# F280041.net
KiCad netlist of a schematic drawn in Altium Designer
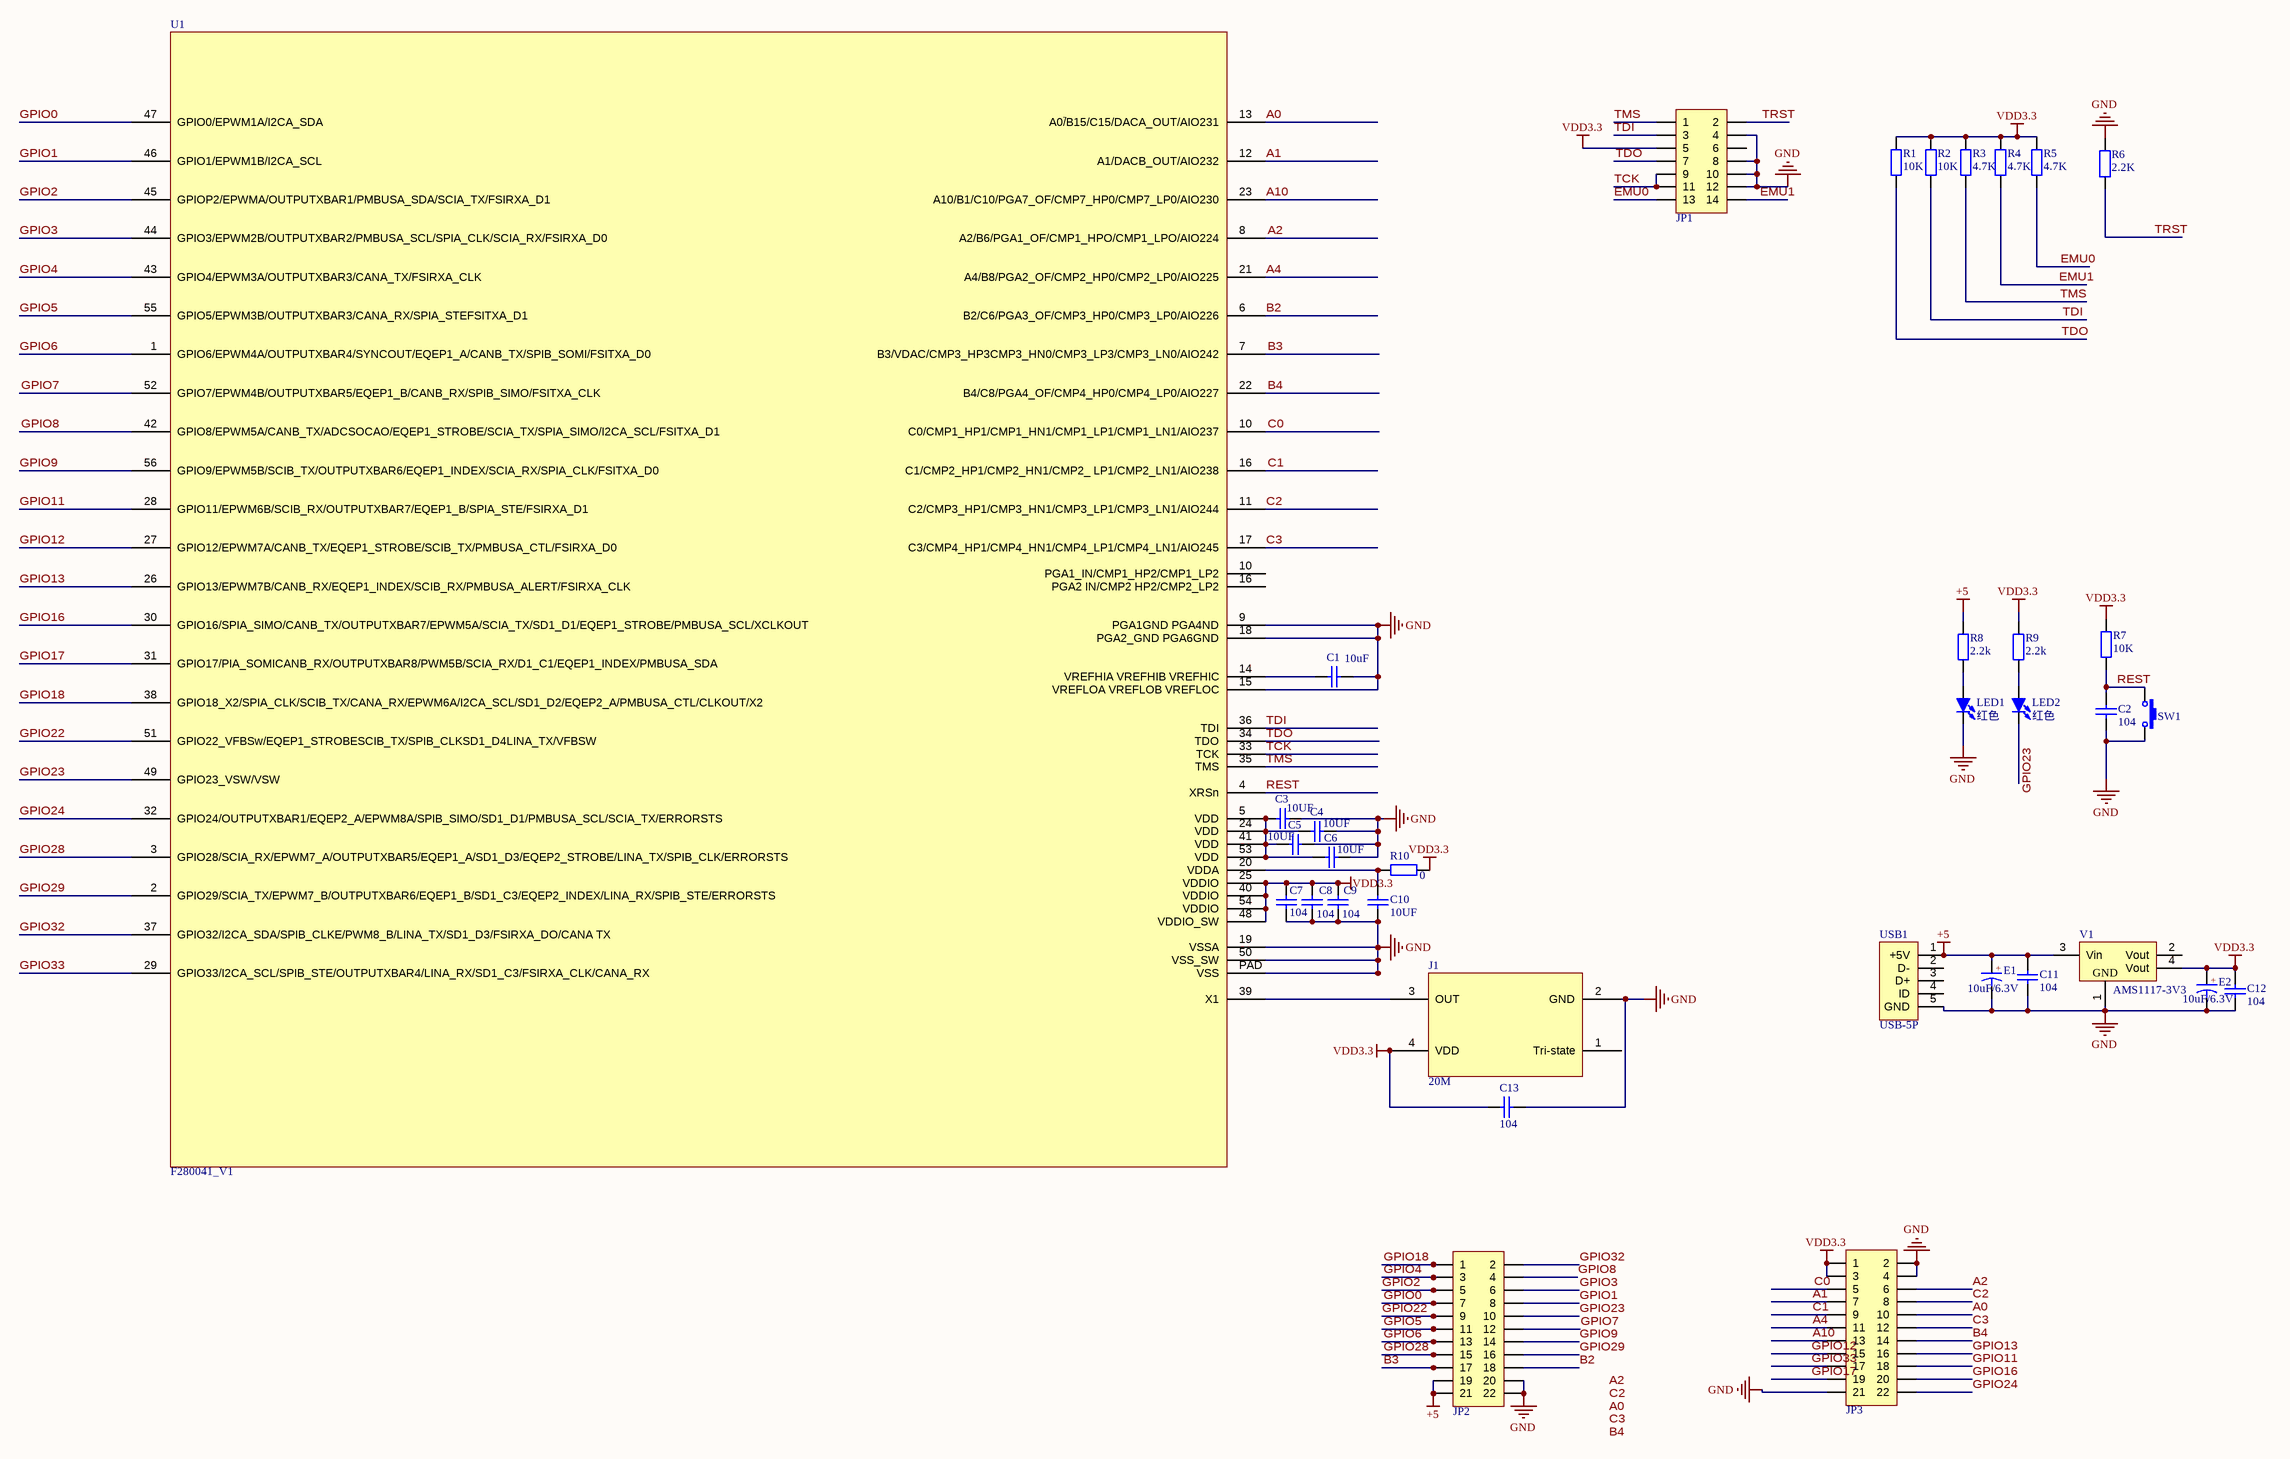
[diagram p0: F280041.SchDoc]

(export (version "E")
  (design (tool "Eeschema 10.0.6"))
  (components
    (comp (ref "C1")
      (value "10uF")
      (footprint "C0603_M")
      (description "贴片电容")
      (libsource (lib "0.1 - 电阻-电容-电感-磁珠-电位器") (part "C"))
    )
    (comp (ref "C2")
      (value "104")
      (footprint "C0603_M")
      (description "贴片电容")
      (libsource (lib "0.1 - 电阻-电容-电感-磁珠-电位器") (part "C"))
    )
    (comp (ref "C3")
      (value "10UF")
      (footprint "C0603_M")
      (description "贴片电容")
      (libsource (lib "0.1 - 电阻-电容-电感-磁珠-电位器") (part "C"))
    )
    (comp (ref "C4")
      (value "10UF")
      (footprint "C0603_M")
      (description "贴片电容")
      (libsource (lib "0.1 - 电阻-电容-电感-磁珠-电位器") (part "C"))
    )
    (comp (ref "C5")
      (value "10UF")
      (footprint "C0603_M")
      (description "贴片电容")
      (libsource (lib "0.1 - 电阻-电容-电感-磁珠-电位器") (part "C"))
    )
    (comp (ref "C6")
      (value "10UF")
      (footprint "C0603_M")
      (description "贴片电容")
      (libsource (lib "0.1 - 电阻-电容-电感-磁珠-电位器") (part "C"))
    )
    (comp (ref "C7")
      (value "104")
      (footprint "C0603_M")
      (description "贴片电容")
      (libsource (lib "0.1 - 电阻-电容-电感-磁珠-电位器") (part "C"))
    )
    (comp (ref "C8")
      (value "104")
      (footprint "C0603_M")
      (description "贴片电容")
      (libsource (lib "0.1 - 电阻-电容-电感-磁珠-电位器") (part "C"))
    )
    (comp (ref "C9")
      (value "104")
      (footprint "C0603_M")
      (description "贴片电容")
      (libsource (lib "0.1 - 电阻-电容-电感-磁珠-电位器") (part "C"))
    )
    (comp (ref "C10")
      (value "10UF")
      (footprint "C0603_M")
      (description "贴片电容")
      (libsource (lib "0.1 - 电阻-电容-电感-磁珠-电位器") (part "C"))
    )
    (comp (ref "C11")
      (value "104")
      (footprint "C0603_M")
      (description "贴片电容")
      (libsource (lib "0.1 - 电阻-电容-电感-磁珠-电位器") (part "C"))
    )
    (comp (ref "C12")
      (value "104")
      (footprint "C0603_M")
      (description "贴片电容")
      (libsource (lib "0.1 - 电阻-电容-电感-磁珠-电位器") (part "C"))
    )
    (comp (ref "C13")
      (value "104")
      (footprint "C0603_M")
      (description "贴片电容")
      (libsource (lib "0.1 - 电阻-电容-电感-磁珠-电位器") (part "C"))
    )
    (comp (ref "E1")
      (value "10uF/6.3V")
      (footprint "C_3216")
      (description "贴片钽电容")
      (libsource (lib "0.1 - 电阻-电容-电感-磁珠-电位器") (part "CT"))
    )
    (comp (ref "E2")
      (value "10uF/6.3V")
      (footprint "C_3216")
      (description "贴片钽电容")
      (libsource (lib "0.1 - 电阻-电容-电感-磁珠-电位器") (part "CT"))
    )
    (comp (ref "J1") (value "20M") (footprint "PCBComponent_1") (libsource (lib "F280041") (part "20M")))
    (comp (ref "JP1")
      (value "JTAG")
      (footprint "HDR2.54-LI-2x7P")
      (description "7*2P接插件")
      (libsource (lib "5.5 - 接插件-脚距2.54 (100mil) ") (part "Header 7X2"))
    )
    (comp (ref "JP2")
      (value "Header 2X11")
      (footprint "HDR2.54-LI-2x11P")
      (description "11*2P接插件")
      (libsource (lib "5.5 - 接插件-脚距2.54 (100mil) ") (part "Header 11X2"))
    )
    (comp (ref "JP3")
      (value "Header 2X11")
      (footprint "HDR2.54-LI-2x11P")
      (description "11*2P接插件")
      (libsource (lib "5.5 - 接插件-脚距2.54 (100mil) ") (part "Header 11X2"))
    )
    (comp (ref "LED1")
      (value "红色")
      (footprint "LED0603_R")
      (description "贴片LED")
      (libsource (lib "0.3 - LED发光二极管") (part "LED-SMD"))
    )
    (comp (ref "LED2")
      (value "红色")
      (footprint "LED0603_R")
      (description "贴片LED")
      (libsource (lib "0.3 - LED发光二极管") (part "LED-SMD"))
    )
    (comp (ref "R1")
      (value "10K")
      (footprint "R0603_M")
      (description "贴片电阻")
      (libsource (lib "0.1 - 电阻-电容-电感-磁珠-电位器") (part "R"))
    )
    (comp (ref "R2")
      (value "10K")
      (footprint "R0603_M")
      (description "贴片电阻")
      (libsource (lib "0.1 - 电阻-电容-电感-磁珠-电位器") (part "R"))
    )
    (comp (ref "R3")
      (value "4.7K")
      (footprint "R0603_M")
      (description "贴片电阻")
      (libsource (lib "0.1 - 电阻-电容-电感-磁珠-电位器") (part "R"))
    )
    (comp (ref "R4")
      (value "4.7K")
      (footprint "R0603_M")
      (description "贴片电阻")
      (libsource (lib "0.1 - 电阻-电容-电感-磁珠-电位器") (part "R"))
    )
    (comp (ref "R5")
      (value "4.7K")
      (footprint "R0603_M")
      (description "贴片电阻")
      (libsource (lib "0.1 - 电阻-电容-电感-磁珠-电位器") (part "R"))
    )
    (comp (ref "R6")
      (value "2.2K")
      (footprint "R0603_M")
      (description "贴片电阻")
      (libsource (lib "0.1 - 电阻-电容-电感-磁珠-电位器") (part "R"))
    )
    (comp (ref "R7")
      (value "10K")
      (footprint "R0603_M")
      (description "贴片电阻")
      (libsource (lib "0.1 - 电阻-电容-电感-磁珠-电位器") (part "R"))
    )
    (comp (ref "R8")
      (value "2.2k")
      (footprint "R0603_M")
      (description "贴片电阻")
      (libsource (lib "0.1 - 电阻-电容-电感-磁珠-电位器") (part "R"))
    )
    (comp (ref "R9")
      (value "2.2k")
      (footprint "R0603_M")
      (description "贴片电阻")
      (libsource (lib "0.1 - 电阻-电容-电感-磁珠-电位器") (part "R"))
    )
    (comp (ref "R10")
      (value "0")
      (footprint "R0603_M")
      (description "贴片电阻")
      (libsource (lib "0.1 - 电阻-电容-电感-磁珠-电位器") (part "R"))
    )
    (comp (ref "SW1")
      (value "3x6x5")
      (footprint "SW SMD-3*6*2.5")
      (description "微动开关")
      (libsource (lib "0.7 - 常用按键-开关-蜂鸣器-电池-测试点") (part "SW-PB"))
    )
    (comp (ref "U1")
      (value "F280041_V1")
      (footprint "QFN40P700X700X100_HS-57N")
      (libsource (lib "F280041") (part "F280041_V1"))
    )
    (comp (ref "USB1")
      (value "USB-5P")
      (footprint "USB-MICRO_A")
      (description "微型USB母座")
      (libsource (lib "0.8 - 以太网-音频-Type-C USB插座") (part "USB-5P"))
    )
    (comp (ref "V1")
      (value "AMS1117-3V3")
      (footprint "SOT223_M")
      (description "三端稳压芯片")
      (libsource (lib "1.1 - 电源类芯片") (part "AMS1117"))
    )
  )
  (nets
    (net (code "1") (name "+5") (class "Default")
      (node (ref "C11") (pin "2") (pinfunction "2_2") (pintype "passive"))
      (node (ref "E1") (pin "1") (pinfunction "A_1") (pintype "passive"))
      (node (ref "JP2") (pin "19") (pinfunction "19_19") (pintype "passive"))
      (node (ref "JP2") (pin "21") (pinfunction "21_21") (pintype "passive"))
      (node (ref "R8") (pin "2") (pinfunction "2_2") (pintype "passive"))
      (node (ref "USB1") (pin "1") (pinfunction "+5V_1") (pintype "passive"))
      (node (ref "V1") (pin "3") (pinfunction "Vin_3") (pintype "passive"))
    )
    (net (code "2") (name "/A0") (class "Default")
      (node (ref "JP3") (pin "10") (pinfunction "10_10") (pintype "passive"))
      (node (ref "U1") (pin "13") (pinfunction "A0~{/}B15/C15/DACA_OUT/AIO231_13") (pintype "passive"))
    )
    (net (code "3") (name "/A1") (class "Default")
      (node (ref "JP3") (pin "7") (pinfunction "7_7") (pintype "passive"))
      (node (ref "U1") (pin "12") (pinfunction "A1/DACB_OUT/AIO232_12") (pintype "passive"))
    )
    (net (code "4") (name "/A2") (class "Default")
      (node (ref "JP3") (pin "6") (pinfunction "6_6") (pintype "passive"))
      (node (ref "U1") (pin "8") (pinfunction "A2/B6/PGA1_OF/CMP1_HPO/CMP1_LPO/AIO224_8") (pintype "passive"))
    )
    (net (code "5") (name "/A4") (class "Default")
      (node (ref "JP3") (pin "11") (pinfunction "11_11") (pintype "passive"))
      (node (ref "U1") (pin "21") (pinfunction "A4/B8/PGA2_OF/CMP2_HP0/CMP2_LP0/AIO225_21") (pintype "passive"))
    )
    (net (code "6") (name "/A10") (class "Default")
      (node (ref "JP3") (pin "13") (pinfunction "13_13") (pintype "passive"))
      (node (ref "U1") (pin "23") (pinfunction "A10/B1/C10/PGA7_OF/CMP7_HP0/CMP7_LP0/AIO230_23") (pintype "passive"))
    )
    (net (code "7") (name "/B2") (class "Default")
      (node (ref "JP2") (pin "18") (pinfunction "18_18") (pintype "passive"))
      (node (ref "U1") (pin "6") (pinfunction "B2/C6/PGA3_OF/CMP3_HP0/CMP3_LP0/AIO226_6") (pintype "passive"))
    )
    (net (code "8") (name "/B3") (class "Default")
      (node (ref "JP2") (pin "17") (pinfunction "17_17") (pintype "passive"))
      (node (ref "U1") (pin "7") (pinfunction "B3/VDAC/CMP3_HP3CMP3_HN0/CMP3_LP3/CMP3_LN0/AIO242_7") (pintype "passive"))
    )
    (net (code "9") (name "/B4") (class "Default")
      (node (ref "JP3") (pin "14") (pinfunction "14_14") (pintype "passive"))
      (node (ref "U1") (pin "22") (pinfunction "B4/C8/PGA4_OF/CMP4_HP0/CMP4_LP0/AIO227_22") (pintype "passive"))
    )
    (net (code "10") (name "/C0") (class "Default")
      (node (ref "JP3") (pin "5") (pinfunction "5_5") (pintype "passive"))
      (node (ref "U1") (pin "10") (pinfunction "C0/CMP1_HP1/CMP1_HN1/CMP1_LP1/CMP1_LN1/AIO237_10") (pintype "passive"))
    )
    (net (code "11") (name "/C1") (class "Default")
      (node (ref "JP3") (pin "9") (pinfunction "9_9") (pintype "passive"))
      (node (ref "U1") (pin "16") (pinfunction "C1/CMP2_HP1/CMP2_HN1/CMP2__LP1/CMP2_LN1/AIO238_16") (pintype "passive"))
    )
    (net (code "12") (name "/C2") (class "Default")
      (node (ref "JP3") (pin "8") (pinfunction "8_8") (pintype "passive"))
      (node (ref "U1") (pin "11") (pinfunction "C2/CMP3_HP1/CMP3_HN1/CMP3_LP1/CMP3_LN1/AIO244_11") (pintype "passive"))
    )
    (net (code "13") (name "/C3") (class "Default")
      (node (ref "JP3") (pin "12") (pinfunction "12_12") (pintype "passive"))
      (node (ref "U1") (pin "17") (pinfunction "C3/CMP4_HP1/CMP4_HN1/CMP4_LP1/CMP4_LN1/AIO245_17") (pintype "passive"))
    )
    (net (code "14") (name "/EMU0") (class "Default")
      (node (ref "JP1") (pin "13") (pinfunction "13_13") (pintype "passive"))
      (node (ref "R5") (pin "2") (pinfunction "2_2") (pintype "passive"))
    )
    (net (code "15") (name "/EMU1") (class "Default")
      (node (ref "JP1") (pin "14") (pinfunction "14_14") (pintype "passive"))
      (node (ref "R4") (pin "2") (pinfunction "2_2") (pintype "passive"))
    )
    (net (code "16") (name "/GPIO0") (class "Default")
      (node (ref "JP2") (pin "7") (pinfunction "7_7") (pintype "passive"))
      (node (ref "U1") (pin "47") (pinfunction "GPIO0/EPWM1A/I2CA_SDA_47") (pintype "passive"))
    )
    (net (code "17") (name "/GPIO1") (class "Default")
      (node (ref "JP2") (pin "8") (pinfunction "8_8") (pintype "passive"))
      (node (ref "U1") (pin "46") (pinfunction "GPIO1/EPWM1B/I2CA_SCL_46") (pintype "passive"))
    )
    (net (code "18") (name "/GPIO2") (class "Default")
      (node (ref "JP2") (pin "5") (pinfunction "5_5") (pintype "passive"))
      (node (ref "U1") (pin "45") (pinfunction "GPIOP2/EPWMA/OUTPUTXBAR1/PMBUSA_SDA/SCIA_TX/FSIRXA_D1_45") (pintype "passive"))
    )
    (net (code "19") (name "/GPIO3") (class "Default")
      (node (ref "JP2") (pin "6") (pinfunction "6_6") (pintype "passive"))
      (node (ref "U1") (pin "44") (pinfunction "GPIO3/EPWM2B/OUTPUTXBAR2/PMBUSA_SCL/SPIA_CLK/SCIA_RX/FSIRXA_D0_44") (pintype "passive"))
    )
    (net (code "20") (name "/GPIO4") (class "Default")
      (node (ref "JP2") (pin "3") (pinfunction "3_3") (pintype "passive"))
      (node (ref "U1") (pin "43") (pinfunction "GPIO4/EPWM3A/OUTPUTXBAR3/CANA_TX/FSIRXA_CLK_43") (pintype "passive"))
    )
    (net (code "21") (name "/GPIO5") (class "Default")
      (node (ref "JP2") (pin "11") (pinfunction "11_11") (pintype "passive"))
      (node (ref "U1") (pin "55") (pinfunction "GPIO5/EPWM3B/OUTPUTXBAR3/CANA_RX/SPIA_STEFSITXA_D1_55") (pintype "passive"))
    )
    (net (code "22") (name "/GPIO6") (class "Default")
      (node (ref "JP2") (pin "13") (pinfunction "13_13") (pintype "passive"))
      (node (ref "U1") (pin "1") (pinfunction "GPIO6/EPWM4A/OUTPUTXBAR4/SYNCOUT/EQEP1_A/CANB_TX/SPIB_SOMI/FSITXA_D0_1") (pintype "passive"))
    )
    (net (code "23") (name "/GPIO7") (class "Default")
      (node (ref "JP2") (pin "12") (pinfunction "12_12") (pintype "passive"))
      (node (ref "U1") (pin "52") (pinfunction "GPIO7/EPWM4B/OUTPUTXBAR5/EQEP1_B/CANB_RX/SPIB_SIMO/FSITXA_CLK_52") (pintype "passive"))
    )
    (net (code "24") (name "/GPIO8") (class "Default")
      (node (ref "JP2") (pin "4") (pinfunction "4_4") (pintype "passive"))
      (node (ref "U1") (pin "42") (pinfunction "GPIO8/EPWM5A/CANB_TX/ADCSOCAO/EQEP1_STROBE/SCIA_TX/SPIA_SIMO/I2CA_SCL/FSITXA_D1_42") (pintype "passive"))
    )
    (net (code "25") (name "/GPIO9") (class "Default")
      (node (ref "JP2") (pin "14") (pinfunction "14_14") (pintype "passive"))
      (node (ref "U1") (pin "56") (pinfunction "GPIO9/EPWM5B/SCIB_TX/OUTPUTXBAR6/EQEP1_INDEX/SCIA_RX/SPIA_CLK/FSITXA_D0_56") (pintype "passive"))
    )
    (net (code "26") (name "/GPIO11") (class "Default")
      (node (ref "JP3") (pin "18") (pinfunction "18_18") (pintype "passive"))
      (node (ref "U1") (pin "28") (pinfunction "GPIO11/EPWM6B/SCIB_RX/OUTPUTXBAR7/EQEP1_B/SPIA_STE/FSIRXA_D1_28") (pintype "passive"))
    )
    (net (code "27") (name "/GPIO12") (class "Default")
      (node (ref "JP3") (pin "15") (pinfunction "15_15") (pintype "passive"))
      (node (ref "U1") (pin "27") (pinfunction "GPIO12/EPWM7A/CANB_TX/EQEP1_STROBE/SCIB_TX/PMBUSA_CTL/FSIRXA_D0_27") (pintype "passive"))
    )
    (net (code "28") (name "/GPIO13") (class "Default")
      (node (ref "JP3") (pin "16") (pinfunction "16_16") (pintype "passive"))
      (node (ref "U1") (pin "26") (pinfunction "GPIO13/EPWM7B/CANB_RX/EQEP1_INDEX/SCIB_RX/PMBUSA_ALERT/FSIRXA_CLK_26") (pintype "passive"))
    )
    (net (code "29") (name "/GPIO16") (class "Default")
      (node (ref "JP3") (pin "20") (pinfunction "20_20") (pintype "passive"))
      (node (ref "U1") (pin "30") (pinfunction "GPIO16/SPIA_SIMO/CANB_TX/OUTPUTXBAR7/EPWM5A/SCIA_TX/SD1_D1/EQEP1_STROBE/PMBUSA_SCL/XCLKOUT_30") (pintype "passive"))
    )
    (net (code "30") (name "/GPIO17") (class "Default")
      (node (ref "JP3") (pin "19") (pinfunction "19_19") (pintype "passive"))
      (node (ref "U1") (pin "31") (pinfunction "GPIO17/PIA_SOMICANB_RX/OUTPUTXBAR8/PWM5B/SCIA_RX/D1_C1/EQEP1_INDEX/PMBUSA_SDA_31") (pintype "passive"))
    )
    (net (code "31") (name "/GPIO18") (class "Default")
      (node (ref "JP2") (pin "1") (pinfunction "1_1") (pintype "passive"))
      (node (ref "U1") (pin "38") (pinfunction "GPIO18_X2/SPIA_CLK/SCIB_TX/CANA_RX/EPWM6A/I2CA_SCL/SD1_D2/EQEP2_A/PMBUSA_CTL/CLKOUT/X2_38") (pintype "passive"))
    )
    (net (code "32") (name "/GPIO22") (class "Default")
      (node (ref "JP2") (pin "9") (pinfunction "9_9") (pintype "passive"))
      (node (ref "U1") (pin "51") (pinfunction "GPIO22_VFBSw/EQEP1_STROBESCIB_TX/SPIB_CLKSD1_D4LINA_TX/VFBSW_51") (pintype "passive"))
    )
    (net (code "33") (name "/GPIO23") (class "Default")
      (node (ref "JP2") (pin "10") (pinfunction "10_10") (pintype "passive"))
      (node (ref "LED2") (pin "2") (pinfunction "K_2") (pintype "passive"))
      (node (ref "U1") (pin "49") (pinfunction "GPIO23_VSW/VSW_49") (pintype "passive"))
    )
    (net (code "34") (name "/GPIO24") (class "Default")
      (node (ref "JP3") (pin "22") (pinfunction "22_22") (pintype "passive"))
      (node (ref "U1") (pin "32") (pinfunction "GPIO24/OUTPUTXBAR1/EQEP2_A/EPWM8A/SPIB_SIMO/SD1_D1/PMBUSA_SCL/SCIA_TX/ERRORSTS_32") (pintype "passive"))
    )
    (net (code "35") (name "/GPIO28") (class "Default")
      (node (ref "JP2") (pin "15") (pinfunction "15_15") (pintype "passive"))
      (node (ref "U1") (pin "3") (pinfunction "GPIO28/SCIA_RX/EPWM7_A/OUTPUTXBAR5/EQEP1_A/SD1_D3/EQEP2_STROBE/LINA_TX/SPIB_CLK/ERRORSTS_3") (pintype "passive"))
    )
    (net (code "36") (name "/GPIO29") (class "Default")
      (node (ref "JP2") (pin "16") (pinfunction "16_16") (pintype "passive"))
      (node (ref "U1") (pin "2") (pinfunction "GPIO29/SCIA_TX/EPWM7_B/OUTPUTXBAR6/EQEP1_B/SD1_C3/EQEP2_INDEX/LINA_RX/SPIB_STE/ERRORSTS_2") (pintype "passive"))
    )
    (net (code "37") (name "/GPIO32") (class "Default")
      (node (ref "JP2") (pin "2") (pinfunction "2_2") (pintype "passive"))
      (node (ref "U1") (pin "37") (pinfunction "GPIO32/I2CA_SDA/SPIB_CLKE/PWM8_B/LINA_TX/SD1_D3/FSIRXA_DO/CANA_TX_37") (pintype "passive"))
    )
    (net (code "38") (name "/GPIO33") (class "Default")
      (node (ref "JP3") (pin "17") (pinfunction "17_17") (pintype "passive"))
      (node (ref "U1") (pin "29") (pinfunction "GPIO33/I2CA_SCL/SPIB_STE/OUTPUTXBAR4/LINA_RX/SD1_C3/FSIRXA_CLK/CANA_RX_29") (pintype "passive"))
    )
    (net (code "39") (name "/REST") (class "Default")
      (node (ref "C2") (pin "2") (pinfunction "2_2") (pintype "passive"))
      (node (ref "R7") (pin "1") (pinfunction "1_1") (pintype "passive"))
      (node (ref "SW1") (pin "1") (pinfunction "1_1") (pintype "passive"))
      (node (ref "U1") (pin "4") (pinfunction "XRSn_4") (pintype "passive"))
    )
    (net (code "40") (name "/TCK") (class "Default")
      (node (ref "JP1") (pin "11") (pinfunction "11_11") (pintype "passive"))
      (node (ref "JP1") (pin "9") (pinfunction "9_9") (pintype "passive"))
      (node (ref "U1") (pin "33") (pinfunction "TCK_33") (pintype "passive"))
    )
    (net (code "41") (name "/TDI") (class "Default")
      (node (ref "JP1") (pin "3") (pinfunction "3_3") (pintype "passive"))
      (node (ref "R2") (pin "2") (pinfunction "2_2") (pintype "passive"))
      (node (ref "U1") (pin "36") (pinfunction "TDI_36") (pintype "passive"))
    )
    (net (code "42") (name "/TDO") (class "Default")
      (node (ref "JP1") (pin "7") (pinfunction "7_7") (pintype "passive"))
      (node (ref "R1") (pin "2") (pinfunction "2_2") (pintype "passive"))
      (node (ref "U1") (pin "34") (pinfunction "TDO_34") (pintype "passive"))
    )
    (net (code "43") (name "/TMS") (class "Default")
      (node (ref "JP1") (pin "1") (pinfunction "1_1") (pintype "passive"))
      (node (ref "R3") (pin "2") (pinfunction "2_2") (pintype "passive"))
      (node (ref "U1") (pin "35") (pinfunction "TMS_35") (pintype "passive"))
    )
    (net (code "44") (name "/TRST") (class "Default")
      (node (ref "JP1") (pin "2") (pinfunction "2_2") (pintype "passive"))
      (node (ref "R6") (pin "2") (pinfunction "2_2") (pintype "passive"))
    )
    (net (code "45") (name "GND") (class "Default")
      (node (ref "C1") (pin "2") (pinfunction "2_2") (pintype "passive"))
      (node (ref "C10") (pin "1") (pinfunction "1_1") (pintype "passive"))
      (node (ref "C11") (pin "1") (pinfunction "1_1") (pintype "passive"))
      (node (ref "C12") (pin "1") (pinfunction "1_1") (pintype "passive"))
      (node (ref "C13") (pin "2") (pinfunction "2_2") (pintype "passive"))
      (node (ref "C2") (pin "1") (pinfunction "1_1") (pintype "passive"))
      (node (ref "C3") (pin "2") (pinfunction "2_2") (pintype "passive"))
      (node (ref "C4") (pin "2") (pinfunction "2_2") (pintype "passive"))
      (node (ref "C5") (pin "2") (pinfunction "2_2") (pintype "passive"))
      (node (ref "C6") (pin "2") (pinfunction "2_2") (pintype "passive"))
      (node (ref "C7") (pin "1") (pinfunction "1_1") (pintype "passive"))
      (node (ref "C8") (pin "1") (pinfunction "1_1") (pintype "passive"))
      (node (ref "C9") (pin "1") (pinfunction "1_1") (pintype "passive"))
      (node (ref "E1") (pin "2") (pinfunction "K_2") (pintype "passive"))
      (node (ref "E2") (pin "2") (pinfunction "K_2") (pintype "passive"))
      (node (ref "J1") (pin "2") (pinfunction "GND_2") (pintype "passive"))
      (node (ref "JP1") (pin "10") (pinfunction "10_10") (pintype "passive"))
      (node (ref "JP1") (pin "12") (pinfunction "12_12") (pintype "passive"))
      (node (ref "JP1") (pin "4") (pinfunction "4_4") (pintype "passive"))
      (node (ref "JP1") (pin "8") (pinfunction "8_8") (pintype "passive"))
      (node (ref "JP2") (pin "20") (pinfunction "20_20") (pintype "passive"))
      (node (ref "JP2") (pin "22") (pinfunction "22_22") (pintype "passive"))
      (node (ref "JP3") (pin "2") (pinfunction "2_2") (pintype "passive"))
      (node (ref "JP3") (pin "21") (pinfunction "21_21") (pintype "passive"))
      (node (ref "JP3") (pin "4") (pinfunction "4_4") (pintype "passive"))
      (node (ref "LED1") (pin "2") (pinfunction "K_2") (pintype "passive"))
      (node (ref "R6") (pin "1") (pinfunction "1_1") (pintype "passive"))
      (node (ref "SW1") (pin "2") (pinfunction "2_2") (pintype "passive"))
      (node (ref "U1") (pin "15") (pinfunction "VREFLOA_VREFLOB_VREFLOC_15") (pintype "passive"))
      (node (ref "U1") (pin "18") (pinfunction "PGA2_GND_PGA6GND_18") (pintype "passive"))
      (node (ref "U1") (pin "19") (pinfunction "VSSA_19") (pintype "passive"))
      (node (ref "U1") (pin "50") (pinfunction "VSS_SW_50") (pintype "passive"))
      (node (ref "U1") (pin "9") (pinfunction "PGA1GND_PGA4ND_9") (pintype "passive"))
      (node (ref "U1") (pin "PAD") (pinfunction "VSS_PAD") (pintype "passive"))
      (node (ref "USB1") (pin "5") (pinfunction "GND_5") (pintype "passive"))
      (node (ref "V1") (pin "1") (pinfunction "GND_1") (pintype "passive"))
    )
    (net (code "46") (name "Net-(C3-Pad1)") (class "Default")
      (node (ref "C3") (pin "1") (pinfunction "1_1") (pintype "passive"))
      (node (ref "C4") (pin "1") (pinfunction "1_1") (pintype "passive"))
      (node (ref "C5") (pin "1") (pinfunction "1_1") (pintype "passive"))
      (node (ref "C6") (pin "1") (pinfunction "1_1") (pintype "passive"))
      (node (ref "U1") (pin "24") (pinfunction "VDD_24") (pintype "passive"))
      (node (ref "U1") (pin "41") (pinfunction "VDD_41") (pintype "passive"))
      (node (ref "U1") (pin "5") (pinfunction "VDD_5") (pintype "passive"))
      (node (ref "U1") (pin "53") (pinfunction "VDD_53") (pintype "passive"))
    )
    (net (code "47") (name "Net-(J1-OUT)") (class "Default")
      (node (ref "J1") (pin "3") (pinfunction "OUT_3") (pintype "passive"))
      (node (ref "U1") (pin "39") (pinfunction "X1_39") (pintype "passive"))
    )
    (net (code "48") (name "Net-(LED1-A)") (class "Default")
      (node (ref "LED1") (pin "1") (pinfunction "A_1") (pintype "passive"))
      (node (ref "R8") (pin "1") (pinfunction "1_1") (pintype "passive"))
    )
    (net (code "49") (name "Net-(LED2-A)") (class "Default")
      (node (ref "LED2") (pin "1") (pinfunction "A_1") (pintype "passive"))
      (node (ref "R9") (pin "1") (pinfunction "1_1") (pintype "passive"))
    )
    (net (code "50") (name "Net-(U1-VDDA)") (class "Default")
      (node (ref "C10") (pin "2") (pinfunction "2_2") (pintype "passive"))
      (node (ref "R10") (pin "2") (pinfunction "2_2") (pintype "passive"))
      (node (ref "U1") (pin "20") (pinfunction "VDDA_20") (pintype "passive"))
    )
    (net (code "51") (name "Net-(U1-VREFHIA_VREFHIB_VREFHIC)") (class "Default")
      (node (ref "C1") (pin "1") (pinfunction "1_1") (pintype "passive"))
      (node (ref "U1") (pin "14") (pinfunction "VREFHIA_VREFHIB_VREFHIC_14") (pintype "passive"))
    )
    (net (code "52") (name "VDD3.3") (class "Default")
      (node (ref "C12") (pin "2") (pinfunction "2_2") (pintype "passive"))
      (node (ref "C13") (pin "1") (pinfunction "1_1") (pintype "passive"))
      (node (ref "C7") (pin "2") (pinfunction "2_2") (pintype "passive"))
      (node (ref "C8") (pin "2") (pinfunction "2_2") (pintype "passive"))
      (node (ref "C9") (pin "2") (pinfunction "2_2") (pintype "passive"))
      (node (ref "E2") (pin "1") (pinfunction "A_1") (pintype "passive"))
      (node (ref "J1") (pin "4") (pinfunction "VDD_4") (pintype "passive"))
      (node (ref "JP1") (pin "5") (pinfunction "5_5") (pintype "passive"))
      (node (ref "JP3") (pin "1") (pinfunction "1_1") (pintype "passive"))
      (node (ref "JP3") (pin "3") (pinfunction "3_3") (pintype "passive"))
      (node (ref "R1") (pin "1") (pinfunction "1_1") (pintype "passive"))
      (node (ref "R10") (pin "1") (pinfunction "1_1") (pintype "passive"))
      (node (ref "R2") (pin "1") (pinfunction "1_1") (pintype "passive"))
      (node (ref "R3") (pin "1") (pinfunction "1_1") (pintype "passive"))
      (node (ref "R4") (pin "1") (pinfunction "1_1") (pintype "passive"))
      (node (ref "R5") (pin "1") (pinfunction "1_1") (pintype "passive"))
      (node (ref "R7") (pin "2") (pinfunction "2_2") (pintype "passive"))
      (node (ref "R9") (pin "2") (pinfunction "2_2") (pintype "passive"))
      (node (ref "U1") (pin "25") (pinfunction "VDDIO_25") (pintype "passive"))
      (node (ref "U1") (pin "40") (pinfunction "VDDIO_40") (pintype "passive"))
      (node (ref "U1") (pin "48") (pinfunction "VDDIO_SW_48") (pintype "passive"))
      (node (ref "U1") (pin "54") (pinfunction "VDDIO_54") (pintype "passive"))
      (node (ref "V1") (pin "4") (pinfunction "Vout_4") (pintype "passive"))
    )
    (net (code "53") (name "unconnected-(J1-Tri-state-Pad1)") (class "Default")
      (node (ref "J1") (pin "1") (pinfunction "Tri-state_1") (pintype "passive"))
    )
    (net (code "54") (name "unconnected-(JP1-Pad6)") (class "Default")
      (node (ref "JP1") (pin "6") (pinfunction "6_6") (pintype "passive"))
    )
    (net (code "55") (name "unconnected-(U1-PGA1_IN{slash}CMP1_HP2{slash}CMP1_LP2-Pad10)") (class "Default")
      (node (ref "U1") (pin "10") (pinfunction "PGA1_IN/CMP1_HP2/CMP1_LP2_10") (pintype "passive"))
    )
    (net (code "56") (name "unconnected-(U1-PGA2_IN{slash}CMP2_HP2{slash}CMP2_LP2-Pad16)") (class "Default")
      (node (ref "U1") (pin "16") (pinfunction "PGA2_IN/CMP2_HP2/CMP2_LP2_16") (pintype "passive"))
    )
    (net (code "57") (name "unconnected-(USB1-D+-Pad3)") (class "Default")
      (node (ref "USB1") (pin "3") (pinfunction "D+_3") (pintype "passive"))
    )
    (net (code "58") (name "unconnected-(USB1-D--Pad2)") (class "Default")
      (node (ref "USB1") (pin "2") (pinfunction "D-_2") (pintype "passive"))
    )
    (net (code "59") (name "unconnected-(USB1-ID-Pad4)") (class "Default")
      (node (ref "USB1") (pin "4") (pinfunction "ID_4") (pintype "passive"))
    )
    (net (code "60") (name "unconnected-(V1-Vout-Pad2)") (class "Default")
      (node (ref "V1") (pin "2") (pinfunction "Vout_2") (pintype "passive"))
    )
  )
)
